# OSSI-1_Analog_Temp_Module.net
KiCad netlist of a schematic drawn in EAGLE
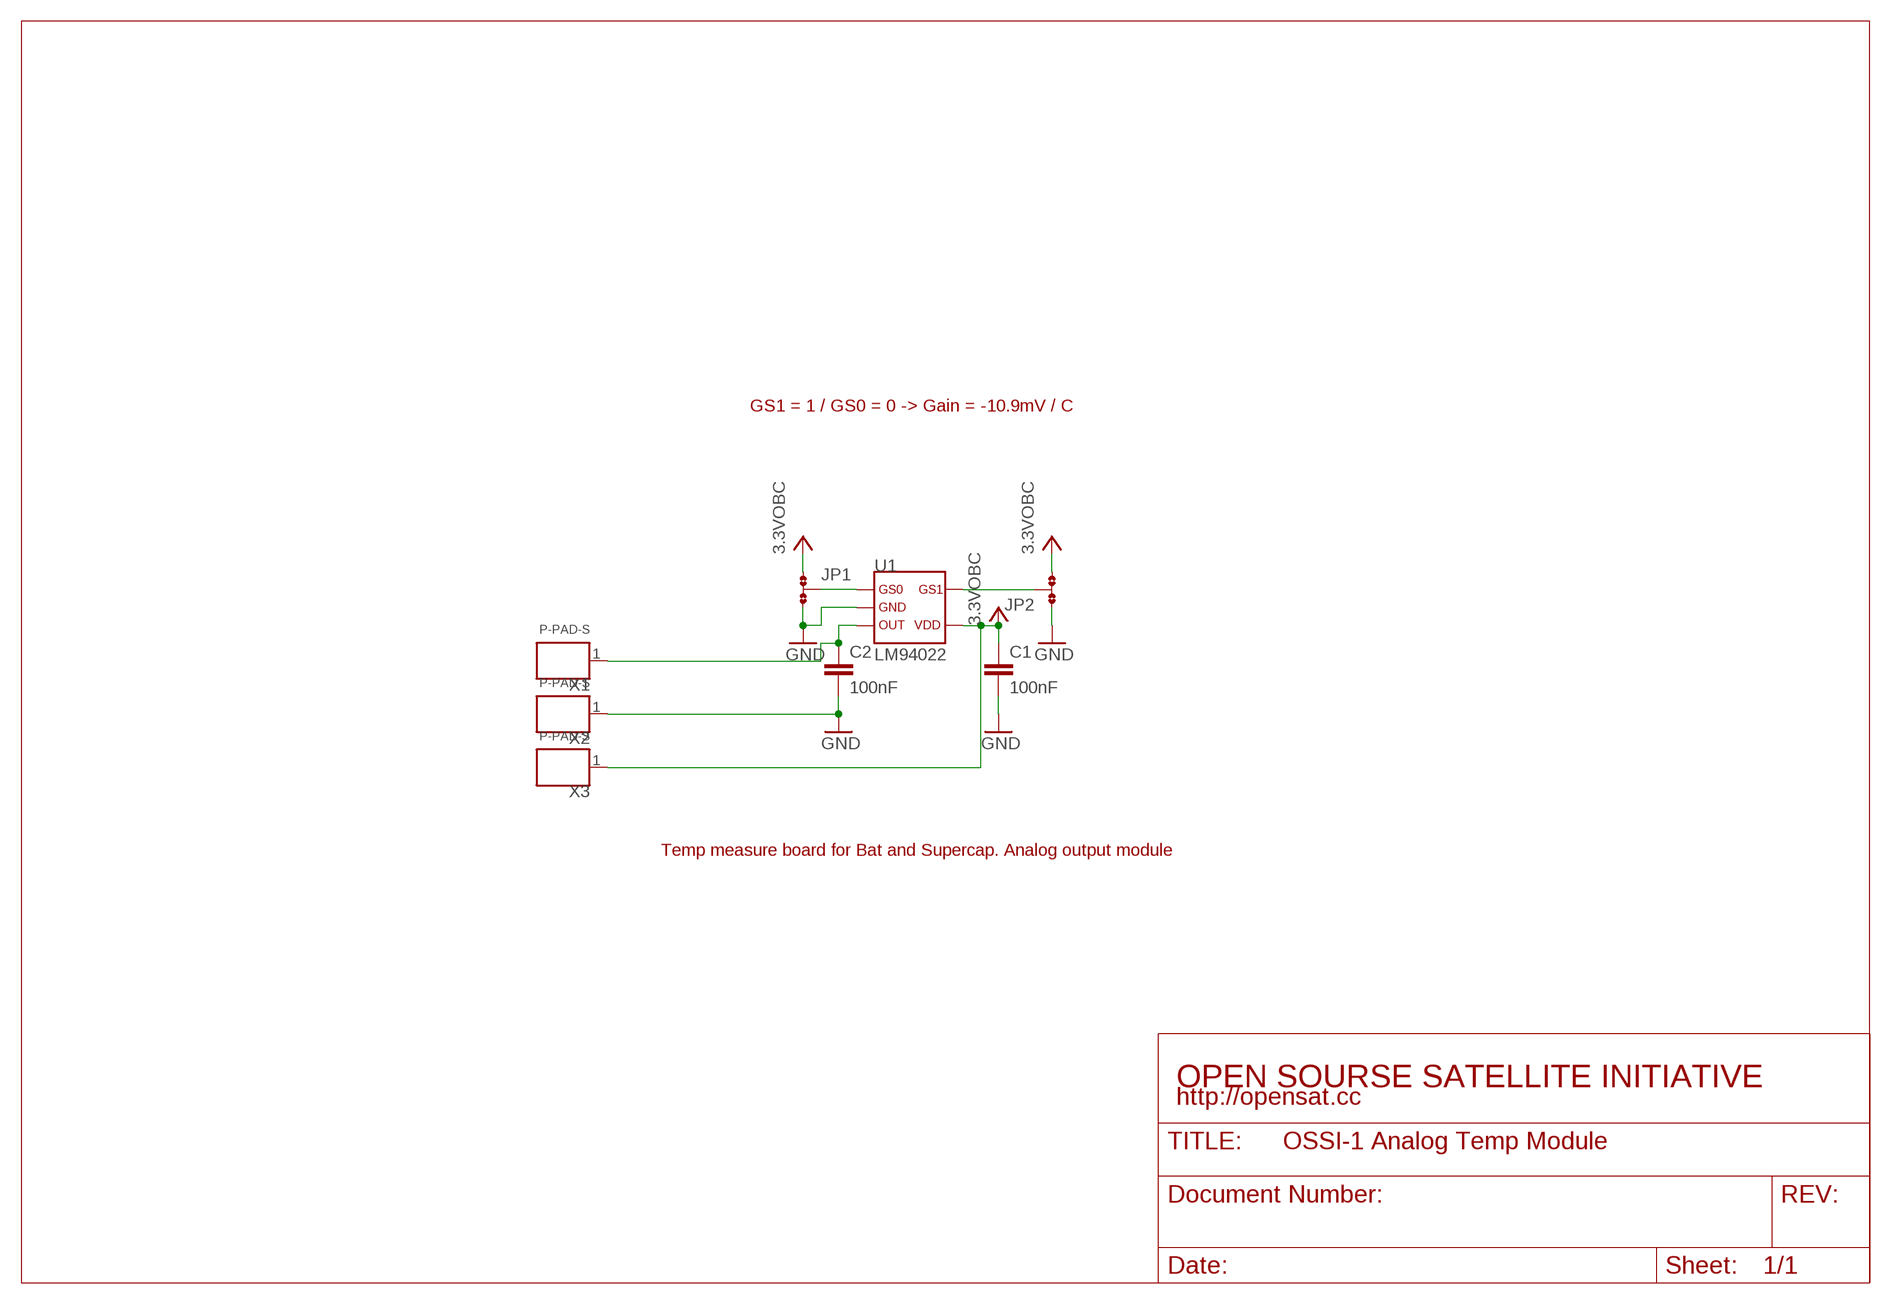
[diagram p0: schematic, sheet 1]

(export (version "E")
  (design (tool "Eeschema 10.0.6"))
  (components
    (comp (ref "C1")
      (value "100nF")
      (footprint "eagle-import:C0603(1608)")
      (libsource (lib "eagle-import") (part "C0603(1608)"))
    )
    (comp (ref "C2")
      (value "100nF")
      (footprint "eagle-import:C0603(1608)")
      (libsource (lib "eagle-import") (part "C0603(1608)"))
    )
    (comp (ref "JP1")
      (value "JP2")
      (footprint "eagle-import:JP2SMD0603")
      (libsource (lib "eagle-import") (part "JP2"))
    )
    (comp (ref "JP2")
      (value "JP2")
      (footprint "eagle-import:JP2SMD0603")
      (libsource (lib "eagle-import") (part "JP2"))
    )
    (comp (ref "U1")
      (value "LM94022")
      (footprint "eagle-import:SC70-5")
      (libsource (lib "eagle-import") (part "LM94022"))
    )
    (comp (ref "X1")
      (value "P-PAD-S")
      (footprint "eagle-import:P-PAD-S")
      (libsource (lib "eagle-import") (part "P-PAD-S"))
    )
    (comp (ref "X2")
      (value "P-PAD-S")
      (footprint "eagle-import:P-PAD-S")
      (libsource (lib "eagle-import") (part "P-PAD-S"))
    )
    (comp (ref "X3")
      (value "P-PAD-S")
      (footprint "eagle-import:P-PAD-S")
      (libsource (lib "eagle-import") (part "P-PAD-S"))
    )
  )
  (nets
    (net (code "1") (name "3.3VOBC") (class "Default")
      (node (ref "C1") (pin "1") (pinfunction "1_1") (pintype "passive"))
      (node (ref "JP1") (pin "1") (pinfunction "1_1") (pintype "passive"))
      (node (ref "JP2") (pin "3") (pinfunction "3_3") (pintype "passive"))
      (node (ref "U1") (pin "P$4") (pinfunction "P$4_P$4") (pintype "power_in"))
      (node (ref "X3") (pin "1") (pinfunction "P$1_1") (pintype "bidirectional"))
    )
    (net (code "2") (name "GND") (class "Default")
      (node (ref "C1") (pin "2") (pinfunction "2_2") (pintype "passive"))
      (node (ref "C2") (pin "2") (pinfunction "2_2") (pintype "passive"))
      (node (ref "JP1") (pin "3") (pinfunction "3_3") (pintype "passive"))
      (node (ref "JP2") (pin "1") (pinfunction "1_1") (pintype "passive"))
      (node (ref "U1") (pin "P$2") (pinfunction "P$2_P$2") (pintype "power_in"))
      (node (ref "X2") (pin "1") (pinfunction "P$1_1") (pintype "bidirectional"))
    )
    (net (code "3") (name "Net-(JP1-Pad2)") (class "Default")
      (node (ref "JP1") (pin "2") (pinfunction "2_2") (pintype "passive"))
      (node (ref "U1") (pin "P$1") (pinfunction "P$1_P$1") (pintype "passive"))
    )
    (net (code "4") (name "Net-(JP2-Pad2)") (class "Default")
      (node (ref "JP2") (pin "2") (pinfunction "2_2") (pintype "passive"))
      (node (ref "U1") (pin "P$5") (pinfunction "P$5_P$5") (pintype "passive"))
    )
    (net (code "5") (name "Net-(X1-P$1)") (class "Default")
      (node (ref "C2") (pin "1") (pinfunction "1_1") (pintype "passive"))
      (node (ref "U1") (pin "P$3") (pinfunction "P$3_P$3") (pintype "output"))
      (node (ref "X1") (pin "1") (pinfunction "P$1_1") (pintype "bidirectional"))
    )
  )
)
